# band-motor-teensy.net
KiCad netlist of a schematic drawn in EAGLE
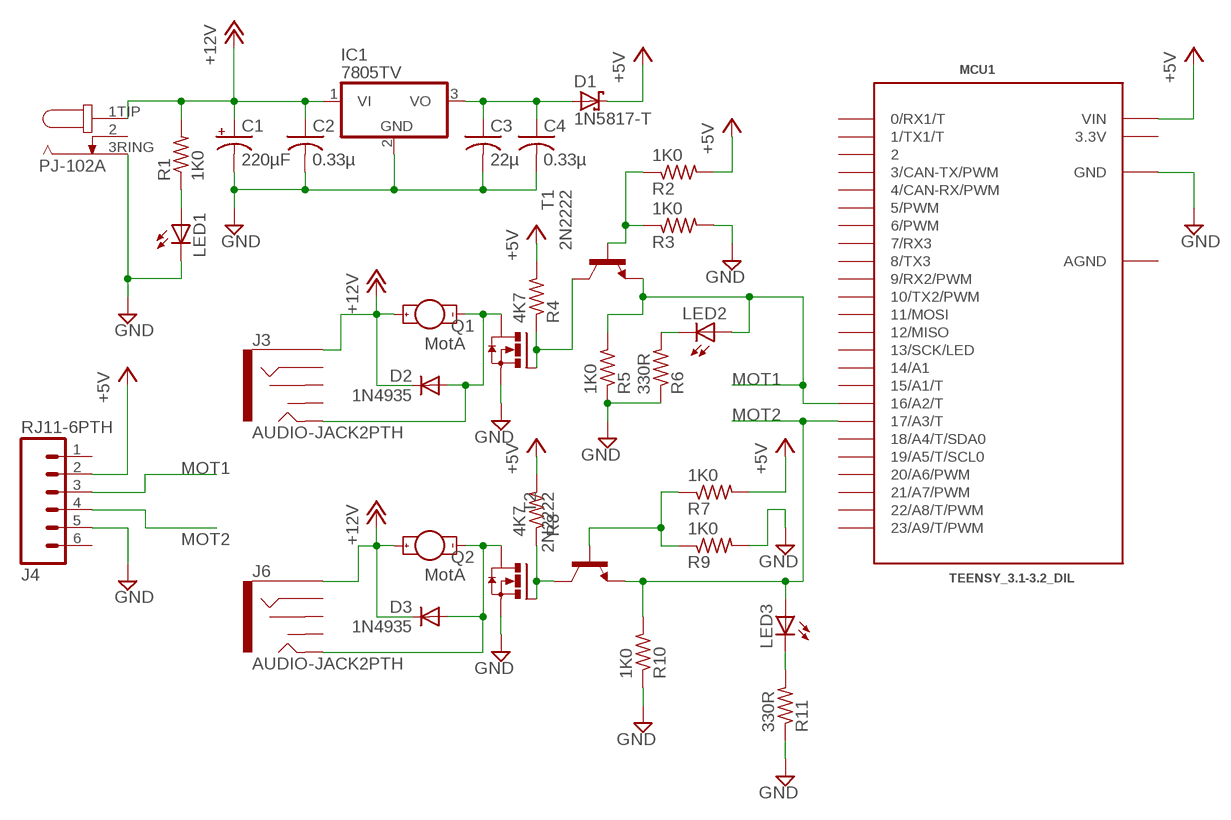
[diagram p0: schematic, sheet 1]

(export (version "E")
  (design (tool "Eeschema 10.0.6"))
  (components
    (comp (ref "C1")
      (value "220µF")
      (footprint "eagle-import:E3,5-8")
      (fields (field (name "MANF") "Panasonic Electronic Components"))
      (libsource (lib "eagle-import") (part "CPOL-USE3.5-8"))
    )
    (comp (ref "C2")
      (value "0.33µ")
      (footprint "eagle-import:C025-050X050")
      (fields (field (name "MANF") "TDK Corporation"))
      (libsource (lib "eagle-import") (part "C-US025-050X050"))
    )
    (comp (ref "C3")
      (value "22µ")
      (footprint "eagle-import:C050-045X075")
      (fields (field (name "MANF") "TDK Corporation"))
      (libsource (lib "eagle-import") (part "C-US050-045X075"))
    )
    (comp (ref "C4")
      (value "0.33µ")
      (footprint "eagle-import:C025-050X050")
      (fields (field (name "MANF") "TDK Corporation"))
      (libsource (lib "eagle-import") (part "C-US025-050X050"))
    )
    (comp (ref "D1")
      (value "1N5817-T")
      (footprint "eagle-import:DO41-7.6")
      (fields (field (name "MANF") "Fairchild Semiconductor"))
      (libsource (lib "eagle-import") (part "1N5817-T"))
    )
    (comp (ref "D2")
      (value "1N4935")
      (footprint "eagle-import:DO41-10")
      (fields (field (name "MANF") "Fairchild Semiconductor"))
      (libsource (lib "eagle-import") (part "1N4004"))
    )
    (comp (ref "D3")
      (value "1N4935")
      (footprint "eagle-import:DO41-10")
      (fields (field (name "MANF") "Fairchild Semiconductor"))
      (libsource (lib "eagle-import") (part "1N4004"))
    )
    (comp (ref "IC1")
      (value "7805TV")
      (footprint "eagle-import:TO220V")
      (fields (field (name "MANF") "Fairchild Semiconductor"))
      (libsource (lib "eagle-import") (part "78TV05"))
    )
    (comp (ref "J1")
      (value "PJ-102A")
      (footprint "eagle-import:PJ-102A")
      (fields (field (name "MANF") "CUI Inc."))
      (libsource (lib "eagle-import") (part "PJ-102A"))
    )
    (comp (ref "J2")
      (value "MotA")
      (footprint "eagle-import:1X02_3.5MM_MOT")
      (fields (field (name "MANF") "On Shore Technology Inc."))
      (libsource (lib "eagle-import") (part "1X02_3.5MM_MOT"))
    )
    (comp (ref "J3")
      (value "AUDIO-JACK2PTH")
      (footprint "eagle-import:AUDIO-JACK")
      (fields (field (name "MANF") "CUI Inc."))
      (libsource (lib "eagle-import") (part "AUDIO-JACK2PTH"))
    )
    (comp (ref "J4")
      (value "RJ11-6PTH")
      (footprint "eagle-import:RJ11-6")
      (fields (field (name "MANF") "Assmann WSW Components"))
      (libsource (lib "eagle-import") (part "RJ11-6PTH"))
    )
    (comp (ref "J5")
      (value "MotA")
      (footprint "eagle-import:1X02_3.5MM_MOT")
      (fields (field (name "MANF") "On Shore Technology Inc."))
      (libsource (lib "eagle-import") (part "1X02_3.5MM_MOT"))
    )
    (comp (ref "J6")
      (value "AUDIO-JACK2PTH")
      (footprint "eagle-import:AUDIO-JACK")
      (fields (field (name "MANF") "CUI Inc."))
      (libsource (lib "eagle-import") (part "AUDIO-JACK2PTH"))
    )
    (comp (ref "LED1")
      (value "LED5MM")
      (footprint "eagle-import:LED5MM")
      (fields (field (name "MANF") "Kingbright"))
      (libsource (lib "eagle-import") (part "LED5MM"))
    )
    (comp (ref "LED2")
      (value "LED3MM")
      (footprint "eagle-import:LED3MM")
      (fields (field (name "MANF") "Kingbright"))
      (libsource (lib "eagle-import") (part "LED3MM"))
    )
    (comp (ref "LED3")
      (value "LED3MM")
      (footprint "eagle-import:LED3MM")
      (fields (field (name "MANF") "Kingbright"))
      (libsource (lib "eagle-import") (part "LED3MM"))
    )
    (comp (ref "MCU1")
      (value "TEENSY_3.1-3.2_DIL")
      (footprint "eagle-import:TEENSY_3.0-3.2&LC_DIL")
      (fields (field (name "MANF") "Samtec Inc."))
      (libsource (lib "eagle-import") (part "TEENSY_3.1-3.2_DIL"))
    )
    (comp (ref "Q1")
      (value "IRLB8721")
      (footprint "eagle-import:TO220BV")
      (fields (field (name "MANF") "International Rectifier"))
      (libsource (lib "eagle-import") (part "IRLB8721"))
    )
    (comp (ref "Q2")
      (value "IRLB8721")
      (footprint "eagle-import:TO220BV")
      (fields (field (name "MANF") "International Rectifier"))
      (libsource (lib "eagle-import") (part "IRLB8721"))
    )
    (comp (ref "R1")
      (value "1K0")
      (footprint "eagle-import:0207_9")
      (fields (field (name "MANF") "Stackpole Electronics Inc."))
      (libsource (lib "eagle-import") (part "R-US_0207/9"))
    )
    (comp (ref "R2")
      (value "1K0")
      (footprint "eagle-import:0207_10")
      (fields (field (name "MANF") "Stackpole Electronics Inc"))
      (libsource (lib "eagle-import") (part "R-US_0207/10"))
    )
    (comp (ref "R3")
      (value "1K0")
      (footprint "eagle-import:0207_10")
      (fields (field (name "MANF") "Stackpole Electronics Inc"))
      (libsource (lib "eagle-import") (part "R-US_0207/10"))
    )
    (comp (ref "R4")
      (value "4K7")
      (footprint "eagle-import:0207_10")
      (fields (field (name "MANF") "Stackpole Electronics Inc"))
      (libsource (lib "eagle-import") (part "R-US_0207/10"))
    )
    (comp (ref "R5")
      (value "1K0")
      (footprint "eagle-import:0207_10")
      (fields (field (name "MANF") "Stackpole Electronics Inc"))
      (libsource (lib "eagle-import") (part "R-US_0207/10"))
    )
    (comp (ref "R6")
      (value "330R")
      (footprint "eagle-import:0207_10")
      (fields (field (name "MANF") "Stackpole Electronics Inc"))
      (libsource (lib "eagle-import") (part "R-US_0207/10"))
    )
    (comp (ref "R7")
      (value "1K0")
      (footprint "eagle-import:0207_10")
      (fields (field (name "MANF") "Stackpole Electronics Inc"))
      (libsource (lib "eagle-import") (part "R-US_0207/10"))
    )
    (comp (ref "R8")
      (value "4K7")
      (footprint "eagle-import:0207_10")
      (fields (field (name "MANF") "Stackpole Electronics Inc"))
      (libsource (lib "eagle-import") (part "R-US_0207/10"))
    )
    (comp (ref "R9")
      (value "1K0")
      (footprint "eagle-import:0207_10")
      (fields (field (name "MANF") "Stackpole Electronics Inc"))
      (libsource (lib "eagle-import") (part "R-US_0207/10"))
    )
    (comp (ref "R10")
      (value "1K0")
      (footprint "eagle-import:0207_10")
      (fields (field (name "MANF") "Stackpole Electronics Inc"))
      (libsource (lib "eagle-import") (part "R-US_0207/10"))
    )
    (comp (ref "R11")
      (value "330R")
      (footprint "eagle-import:0207_10")
      (fields (field (name "MANF") "Stackpole Electronics Inc"))
      (libsource (lib "eagle-import") (part "R-US_0207/10"))
    )
    (comp (ref "T1")
      (value "2N2222")
      (footprint "eagle-import:TO92-EBC-OVAL")
      (fields (field (name "MANF") "Fairchild Semiconductor"))
      (libsource (lib "eagle-import") (part "2N2222"))
    )
    (comp (ref "T2")
      (value "2N2222")
      (footprint "eagle-import:TO92-EBC-OVAL")
      (fields (field (name "MANF") "Fairchild Semiconductor"))
      (libsource (lib "eagle-import") (part "2N2222"))
    )
  )
  (nets
    (net (code "1") (name "+5V") (class "Default")
      (node (ref "D1") (pin "C") (pinfunction "C_C") (pintype "passive"))
      (node (ref "J4") (pin "2") (pinfunction "2_2") (pintype "passive"))
      (node (ref "MCU1") (pin "VIN") (pinfunction "VIN_VIN") (pintype "power_in"))
      (node (ref "R2") (pin "2") (pinfunction "2_2") (pintype "passive"))
      (node (ref "R4") (pin "2") (pinfunction "2_2") (pintype "passive"))
      (node (ref "R7") (pin "2") (pinfunction "2_2") (pintype "passive"))
      (node (ref "R8") (pin "2") (pinfunction "2_2") (pintype "passive"))
    )
    (net (code "2") (name "+12V") (class "Default")
      (node (ref "C1") (pin "+") (pinfunction "+_+") (pintype "passive"))
      (node (ref "C2") (pin "1") (pinfunction "1_1") (pintype "passive"))
      (node (ref "D2") (pin "C") (pinfunction "C_C") (pintype "passive"))
      (node (ref "D3") (pin "C") (pinfunction "C_C") (pintype "passive"))
      (node (ref "IC1") (pin "1") (pinfunction "VI_1") (pintype "input"))
      (node (ref "J1") (pin "1TIP") (pinfunction "3TIP_1TIP") (pintype "passive"))
      (node (ref "J2") (pin "1A") (pinfunction "+_1A") (pintype "bidirectional"))
      (node (ref "J3") (pin "SLEEVE") (pinfunction "SLEEVE_SLEEVE") (pintype "bidirectional"))
      (node (ref "J5") (pin "1A") (pinfunction "+_1A") (pintype "bidirectional"))
      (node (ref "J6") (pin "SLEEVE") (pinfunction "SLEEVE_SLEEVE") (pintype "bidirectional"))
      (node (ref "R1") (pin "2") (pinfunction "2_2") (pintype "passive"))
    )
    (net (code "3") (name "/3.3V") (class "Default")
      (node (ref "MCU1") (pin "3.3V") (pinfunction "3.3V_3.3V") (pintype "power_in"))
    )
    (net (code "4") (name "/AGND") (class "Default")
      (node (ref "MCU1") (pin "AGND") (pinfunction "AGND_AGND") (pintype "power_in"))
    )
    (net (code "5") (name "/MOT1") (class "Default")
      (node (ref "J4") (pin "3") (pinfunction "3_3") (pintype "passive"))
      (node (ref "LED2") (pin "A") (pinfunction "A_A") (pintype "passive"))
      (node (ref "MCU1") (pin "16/A2") (pinfunction "16/A2/T_16/A2") (pintype "bidirectional"))
      (node (ref "R5") (pin "2") (pinfunction "2_2") (pintype "passive"))
      (node (ref "T1") (pin "E") (pinfunction "E_E") (pintype "passive"))
    )
    (net (code "6") (name "/MOT2") (class "Default")
      (node (ref "J4") (pin "4") (pinfunction "4_4") (pintype "passive"))
      (node (ref "LED3") (pin "A") (pinfunction "A_A") (pintype "passive"))
      (node (ref "MCU1") (pin "17/A3") (pinfunction "17/A3/T_17/A3") (pintype "bidirectional"))
      (node (ref "R10") (pin "2") (pinfunction "2_2") (pintype "passive"))
      (node (ref "T2") (pin "E") (pinfunction "E_E") (pintype "passive"))
    )
    (net (code "7") (name "GND") (class "Default")
      (node (ref "C1") (pin "-") (pinfunction "-_-") (pintype "passive"))
      (node (ref "C2") (pin "2") (pinfunction "2_2") (pintype "passive"))
      (node (ref "C3") (pin "2") (pinfunction "2_2") (pintype "passive"))
      (node (ref "C4") (pin "2") (pinfunction "2_2") (pintype "passive"))
      (node (ref "IC1") (pin "2") (pinfunction "GND_2") (pintype "passive"))
      (node (ref "J1") (pin "3RING") (pinfunction "1RING_3RING") (pintype "passive"))
      (node (ref "J4") (pin "5") (pinfunction "5_5") (pintype "passive"))
      (node (ref "LED1") (pin "K") (pinfunction "C_K") (pintype "passive"))
      (node (ref "MCU1") (pin "GND") (pinfunction "GND_GND") (pintype "power_in"))
      (node (ref "Q1") (pin "S") (pinfunction "S_S") (pintype "passive"))
      (node (ref "Q2") (pin "S") (pinfunction "S_S") (pintype "passive"))
      (node (ref "R10") (pin "1") (pinfunction "1_1") (pintype "passive"))
      (node (ref "R11") (pin "1") (pinfunction "1_1") (pintype "passive"))
      (node (ref "R3") (pin "2") (pinfunction "2_2") (pintype "passive"))
      (node (ref "R5") (pin "1") (pinfunction "1_1") (pintype "passive"))
      (node (ref "R6") (pin "1") (pinfunction "1_1") (pintype "passive"))
      (node (ref "R9") (pin "2") (pinfunction "2_2") (pintype "passive"))
    )
    (net (code "8") (name "Net-(IC1-VO)") (class "Default")
      (node (ref "C3") (pin "1") (pinfunction "1_1") (pintype "passive"))
      (node (ref "C4") (pin "1") (pinfunction "1_1") (pintype "passive"))
      (node (ref "D1") (pin "A") (pinfunction "A_A") (pintype "passive"))
      (node (ref "IC1") (pin "3") (pinfunction "VO_3") (pintype "passive"))
    )
    (net (code "9") (name "Net-(J2--)") (class "Default")
      (node (ref "D2") (pin "A") (pinfunction "A_A") (pintype "passive"))
      (node (ref "J2") (pin "2K") (pinfunction "-_2K") (pintype "bidirectional"))
      (node (ref "J3") (pin "TIP") (pinfunction "TIP_TIP") (pintype "bidirectional"))
      (node (ref "Q1") (pin "D") (pinfunction "D_D") (pintype "passive"))
    )
    (net (code "10") (name "Net-(J5--)") (class "Default")
      (node (ref "D3") (pin "A") (pinfunction "A_A") (pintype "passive"))
      (node (ref "J5") (pin "2K") (pinfunction "-_2K") (pintype "bidirectional"))
      (node (ref "J6") (pin "TIP") (pinfunction "TIP_TIP") (pintype "bidirectional"))
      (node (ref "Q2") (pin "D") (pinfunction "D_D") (pintype "passive"))
    )
    (net (code "11") (name "Net-(LED1-PadA)") (class "Default")
      (node (ref "LED1") (pin "A") (pinfunction "A_A") (pintype "passive"))
      (node (ref "R1") (pin "1") (pinfunction "1_1") (pintype "passive"))
    )
    (net (code "12") (name "Net-(LED2-C)") (class "Default")
      (node (ref "LED2") (pin "K") (pinfunction "C_K") (pintype "passive"))
      (node (ref "R6") (pin "2") (pinfunction "2_2") (pintype "passive"))
    )
    (net (code "13") (name "Net-(LED3-C)") (class "Default")
      (node (ref "LED3") (pin "K") (pinfunction "C_K") (pintype "passive"))
      (node (ref "R11") (pin "2") (pinfunction "2_2") (pintype "passive"))
    )
    (net (code "14") (name "Net-(Q1-PadG)") (class "Default")
      (node (ref "Q1") (pin "G") (pinfunction "G_G") (pintype "passive"))
      (node (ref "R4") (pin "1") (pinfunction "1_1") (pintype "passive"))
      (node (ref "T1") (pin "C") (pinfunction "C_C") (pintype "passive"))
    )
    (net (code "15") (name "Net-(Q2-PadG)") (class "Default")
      (node (ref "Q2") (pin "G") (pinfunction "G_G") (pintype "passive"))
      (node (ref "R8") (pin "1") (pinfunction "1_1") (pintype "passive"))
      (node (ref "T2") (pin "C") (pinfunction "C_C") (pintype "passive"))
    )
    (net (code "16") (name "Net-(R2-Pad1)") (class "Default")
      (node (ref "R2") (pin "1") (pinfunction "1_1") (pintype "passive"))
      (node (ref "R3") (pin "1") (pinfunction "1_1") (pintype "passive"))
      (node (ref "T1") (pin "B") (pinfunction "B_B") (pintype "passive"))
    )
    (net (code "17") (name "Net-(R7-Pad1)") (class "Default")
      (node (ref "R7") (pin "1") (pinfunction "1_1") (pintype "passive"))
      (node (ref "R9") (pin "1") (pinfunction "1_1") (pintype "passive"))
      (node (ref "T2") (pin "B") (pinfunction "B_B") (pintype "passive"))
    )
    (net (code "18") (name "unconnected-(J1-Pad2)") (class "Default")
      (node (ref "J1") (pin "2") (pinfunction "2_2") (pintype "passive"))
    )
    (net (code "19") (name "unconnected-(J3-PadRING)") (class "Default")
      (node (ref "J3") (pin "RING") (pinfunction "RING_RING") (pintype "bidirectional"))
    )
    (net (code "20") (name "unconnected-(J3-PadRSH)") (class "Default")
      (node (ref "J3") (pin "RSH") (pinfunction "RSH_RSH") (pintype "bidirectional"))
    )
    (net (code "21") (name "unconnected-(J3-PadTSH)") (class "Default")
      (node (ref "J3") (pin "TSH") (pinfunction "TSH_TSH") (pintype "bidirectional"))
    )
    (net (code "22") (name "unconnected-(J4-Pad1)") (class "Default")
      (node (ref "J4") (pin "1") (pinfunction "1_1") (pintype "passive"))
    )
    (net (code "23") (name "unconnected-(J4-Pad6)") (class "Default")
      (node (ref "J4") (pin "6") (pinfunction "6_6") (pintype "passive"))
    )
    (net (code "24") (name "unconnected-(J6-PadRING)") (class "Default")
      (node (ref "J6") (pin "RING") (pinfunction "RING_RING") (pintype "bidirectional"))
    )
    (net (code "25") (name "unconnected-(J6-PadRSH)") (class "Default")
      (node (ref "J6") (pin "RSH") (pinfunction "RSH_RSH") (pintype "bidirectional"))
    )
    (net (code "26") (name "unconnected-(J6-PadTSH)") (class "Default")
      (node (ref "J6") (pin "TSH") (pinfunction "TSH_TSH") (pintype "bidirectional"))
    )
    (net (code "27") (name "unconnected-(MCU1-0{slash}RX1{slash}T-Pad0)") (class "Default")
      (node (ref "MCU1") (pin "0") (pinfunction "0/RX1/T_0") (pintype "bidirectional"))
    )
    (net (code "28") (name "unconnected-(MCU1-1{slash}TX1{slash}T-Pad1)") (class "Default")
      (node (ref "MCU1") (pin "1") (pinfunction "1/TX1/T_1") (pintype "bidirectional"))
    )
    (net (code "29") (name "unconnected-(MCU1-3{slash}CAN-TX{slash}PWM-Pad3)") (class "Default")
      (node (ref "MCU1") (pin "3") (pinfunction "3/CAN-TX/PWM_3") (pintype "bidirectional"))
    )
    (net (code "30") (name "unconnected-(MCU1-4{slash}CAN-RX{slash}PWM-Pad4)") (class "Default")
      (node (ref "MCU1") (pin "4") (pinfunction "4/CAN-RX/PWM_4") (pintype "bidirectional"))
    )
    (net (code "31") (name "unconnected-(MCU1-5{slash}PWM-Pad5)") (class "Default")
      (node (ref "MCU1") (pin "5") (pinfunction "5/PWM_5") (pintype "bidirectional"))
    )
    (net (code "32") (name "unconnected-(MCU1-6{slash}PWM-Pad6)") (class "Default")
      (node (ref "MCU1") (pin "6") (pinfunction "6/PWM_6") (pintype "bidirectional"))
    )
    (net (code "33") (name "unconnected-(MCU1-7{slash}RX3-Pad7)") (class "Default")
      (node (ref "MCU1") (pin "7") (pinfunction "7/RX3_7") (pintype "bidirectional"))
    )
    (net (code "34") (name "unconnected-(MCU1-8{slash}TX3-Pad8)") (class "Default")
      (node (ref "MCU1") (pin "8") (pinfunction "8/TX3_8") (pintype "bidirectional"))
    )
    (net (code "35") (name "unconnected-(MCU1-9{slash}RX2{slash}PWM-Pad9)") (class "Default")
      (node (ref "MCU1") (pin "9") (pinfunction "9/RX2/PWM_9") (pintype "bidirectional"))
    )
    (net (code "36") (name "unconnected-(MCU1-10{slash}TX2{slash}PWM-Pad10)") (class "Default")
      (node (ref "MCU1") (pin "10") (pinfunction "10/TX2/PWM_10") (pintype "bidirectional"))
    )
    (net (code "37") (name "unconnected-(MCU1-11{slash}MOSI-Pad11)") (class "Default")
      (node (ref "MCU1") (pin "11") (pinfunction "11/MOSI_11") (pintype "bidirectional"))
    )
    (net (code "38") (name "unconnected-(MCU1-12{slash}MISO-Pad12)") (class "Default")
      (node (ref "MCU1") (pin "12") (pinfunction "12/MISO_12") (pintype "bidirectional"))
    )
    (net (code "39") (name "unconnected-(MCU1-13{slash}SCK{slash}LED-Pad13)") (class "Default")
      (node (ref "MCU1") (pin "13") (pinfunction "13/SCK/LED_13") (pintype "bidirectional"))
    )
    (net (code "40") (name "unconnected-(MCU1-14{slash}A1-Pad14{slash}A0)") (class "Default")
      (node (ref "MCU1") (pin "14/A0") (pinfunction "14/A1_14/A0") (pintype "bidirectional"))
    )
    (net (code "41") (name "unconnected-(MCU1-15{slash}A1{slash}T-Pad15{slash}A1)") (class "Default")
      (node (ref "MCU1") (pin "15/A1") (pinfunction "15/A1/T_15/A1") (pintype "bidirectional"))
    )
    (net (code "42") (name "unconnected-(MCU1-18{slash}A4{slash}T{slash}SDA0-Pad18{slash}A4)") (class "Default")
      (node (ref "MCU1") (pin "18/A4") (pinfunction "18/A4/T/SDA0_18/A4") (pintype "bidirectional"))
    )
    (net (code "43") (name "unconnected-(MCU1-19{slash}A5{slash}T{slash}SCL0-Pad19{slash}A5)") (class "Default")
      (node (ref "MCU1") (pin "19/A5") (pinfunction "19/A5/T/SCL0_19/A5") (pintype "bidirectional"))
    )
    (net (code "44") (name "unconnected-(MCU1-20{slash}A6{slash}PWM-Pad20{slash}A6)") (class "Default")
      (node (ref "MCU1") (pin "20/A6") (pinfunction "20/A6/PWM_20/A6") (pintype "bidirectional"))
    )
    (net (code "45") (name "unconnected-(MCU1-21{slash}A7{slash}PWM-Pad21{slash}A7)") (class "Default")
      (node (ref "MCU1") (pin "21/A7") (pinfunction "21/A7/PWM_21/A7") (pintype "bidirectional"))
    )
    (net (code "46") (name "unconnected-(MCU1-22{slash}A8{slash}T{slash}PWM-Pad22{slash}A8)") (class "Default")
      (node (ref "MCU1") (pin "22/A8") (pinfunction "22/A8/T/PWM_22/A8") (pintype "bidirectional"))
    )
    (net (code "47") (name "unconnected-(MCU1-23{slash}A9{slash}T{slash}PWM-Pad23{slash}A9)") (class "Default")
      (node (ref "MCU1") (pin "23/A9") (pinfunction "23/A9/T/PWM_23/A9") (pintype "bidirectional"))
    )
    (net (code "48") (name "unconnected-(MCU1-Pad2)") (class "Default")
      (node (ref "MCU1") (pin "2") (pinfunction "2_2") (pintype "bidirectional"))
    )
  )
)
